# MAIN.net
KiCad netlist of a schematic drawn in Altium Designer
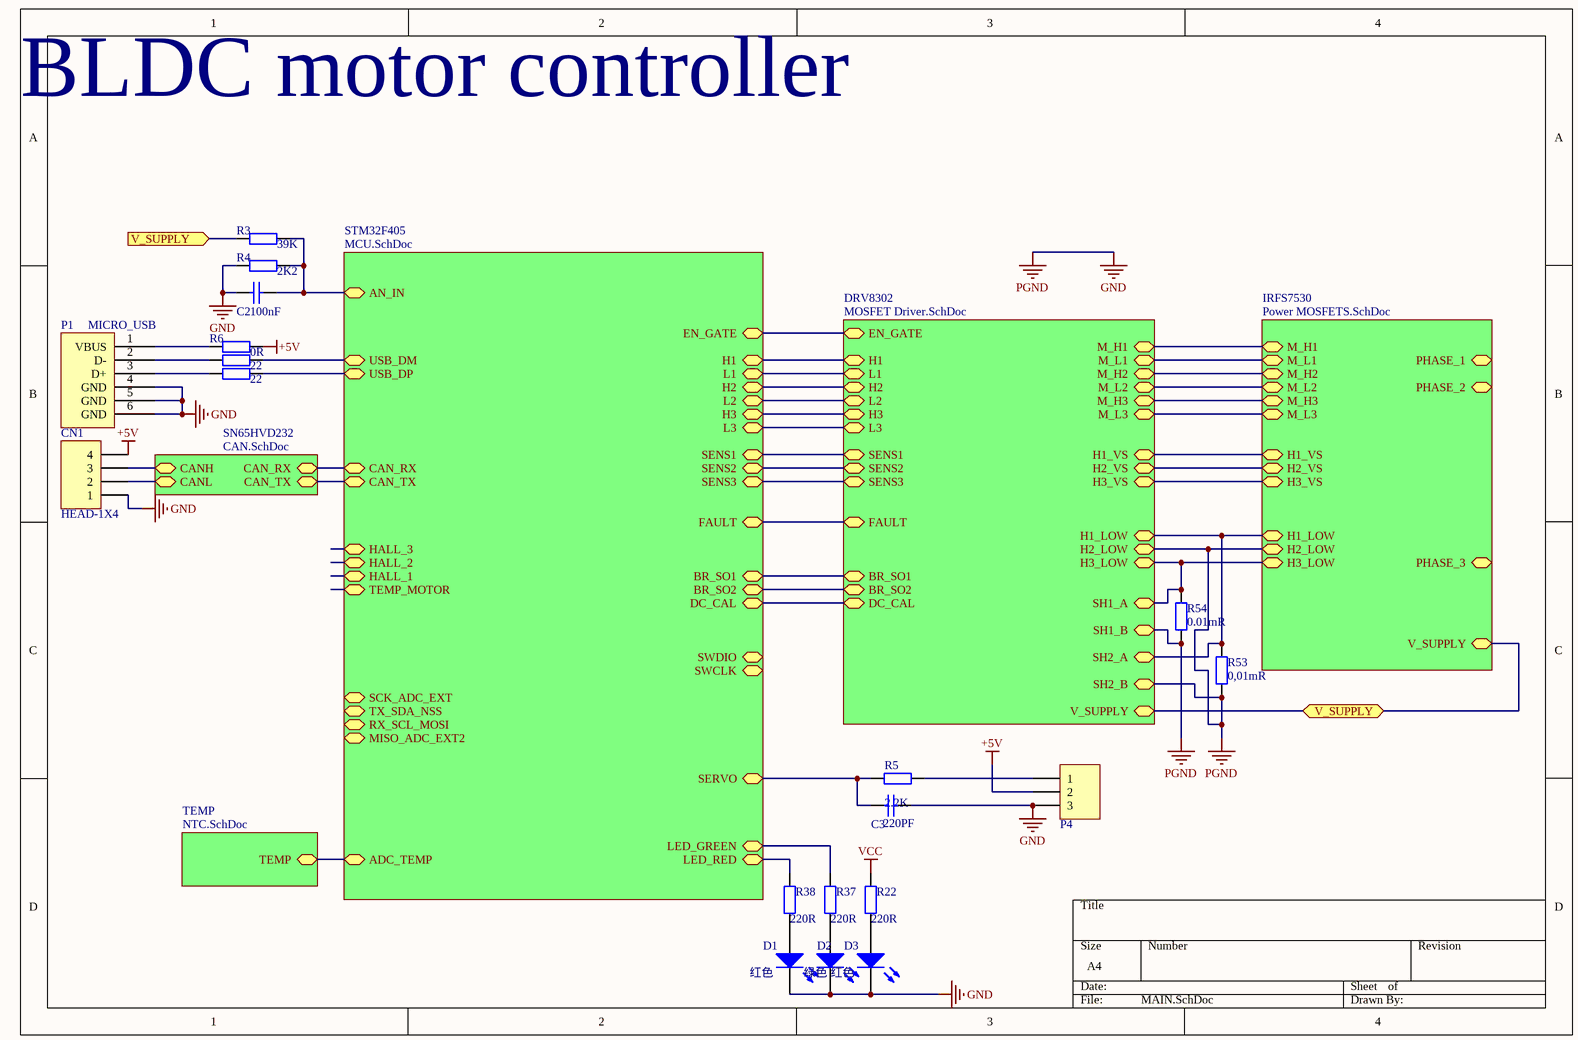
[diagram p0: MAIN.SchDoc]

(export (version "E")
  (design (tool "Eeschema 10.0.6"))
  (components
    (comp (ref "C2")
      (value "100nF")
      (footprint "C-0603")
      (description "Capacitor")
      (fields (field (name "Comment") "CAP") (field (name "PUBLISHER") "Altium Limited"))
      (libsource (lib "TAOXUN") (part "CAP"))
    )
    (comp (ref "C3")
      (value "220PF")
      (footprint "C-0603")
      (description "Capacitor")
      (fields (field (name "PUBLISHER") "Altium Limited"))
      (libsource (lib "TAOXUN") (part "CAP"))
    )
    (comp (ref "CN1")
      (value "HEAD-1X4")
      (footprint "H-1X4")
      (description "Header, 4-Pin")
      (fields (field (name "PUBLISHER") "Altium Limited"))
      (libsource (lib "TAOXUN") (part "HEAD-1X4"))
    )
    (comp (ref "D1")
      (value "红色")
      (footprint "LED0603")
      (description "Typical RED, GREEN, YELLOW, AMBER GaAs LED")
      (fields (field (name "PUBLISHER") "Altium Limited"))
      (libsource (lib "TAOXUN") (part "LED2"))
    )
    (comp (ref "D2")
      (value "绿色")
      (footprint "LED0603")
      (description "Typical RED, GREEN, YELLOW, AMBER GaAs LED")
      (fields (field (name "PUBLISHER") "Altium Limited"))
      (libsource (lib "TAOXUN") (part "LED2"))
    )
    (comp (ref "D3")
      (value "红色")
      (footprint "LED0603")
      (description "Typical RED, GREEN, YELLOW, AMBER GaAs LED")
      (fields (field (name "PUBLISHER") "Altium Limited"))
      (libsource (lib "TAOXUN") (part "LED2"))
    )
    (comp (ref "P1")
      (value "MICRO_USB")
      (footprint "MicroUSB")
      (libsource (lib "Control_PT") (part "MINI_USB"))
    )
    (comp (ref "P4")
      (value "Header 3")
      (footprint "HDR3X1_A")
      (description "接插件")
      (fields (field (name "PUBLISHER") "Altium Limited"))
      (libsource (lib "TAOXUN") (part "Header 3_1"))
    )
    (comp (ref "R3")
      (value "39K")
      (footprint "0402")
      (description "贴片电阻")
      (fields (field (name "PUBLISHER") "Altium Limited"))
      (libsource (lib "TAOXUN") (part "Res1"))
    )
    (comp (ref "R4")
      (value "2K2")
      (footprint "0402")
      (description "贴片电阻")
      (fields (field (name "Comment") "2.2K") (field (name "PUBLISHER") "Altium Limited"))
      (libsource (lib "TAOXUN") (part "Res1"))
    )
    (comp (ref "R5")
      (value "2.2K")
      (footprint "0402")
      (description "贴片电阻")
      (fields (field (name "PUBLISHER") "Altium Limited"))
      (libsource (lib "TAOXUN") (part "Res1"))
    )
    (comp (ref "R6")
      (value "0R")
      (footprint "0603-2")
      (description "贴片电阻")
      (fields (field (name "PUBLISHER") "Altium Limited"))
      (libsource (lib "TAOXUN") (part "Res1"))
    )
    (comp (ref "R14")
      (value "22")
      (footprint "LC-0402")
      (description "贴片电阻")
      (fields (field (name "Comment") "22R") (field (name "PUBLISHER") "Altium Limited"))
      (libsource (lib "TAOXUN") (part "Res1"))
    )
    (comp (ref "R15")
      (value "22")
      (footprint "LC-0402")
      (description "贴片电阻")
      (fields (field (name "Comment") "22R") (field (name "PUBLISHER") "Altium Limited"))
      (libsource (lib "TAOXUN") (part "Res1"))
    )
    (comp (ref "R22")
      (value "220R")
      (footprint "0402")
      (description "贴片电阻")
      (fields (field (name "PUBLISHER") "Altium Limited"))
      (libsource (lib "") (part "Res1_1"))
    )
    (comp (ref "R37")
      (value "220R")
      (footprint "0402")
      (description "贴片电阻")
      (fields (field (name "PUBLISHER") "Altium Limited"))
      (libsource (lib "") (part "Res1_1"))
    )
    (comp (ref "R38")
      (value "220R")
      (footprint "0402")
      (description "贴片电阻")
      (fields (field (name "PUBLISHER") "Altium Limited"))
      (libsource (lib "") (part "Res1_1"))
    )
    (comp (ref "R53")
      (value "0,01mR")
      (footprint "2512")
      (description "贴片电阻")
      (fields (field (name "Comment") "0.001R") (field (name "PUBLISHER") "Altium Limited"))
      (libsource (lib "") (part "Res1_2"))
    )
    (comp (ref "R54")
      (value "0.01mR")
      (footprint "2512")
      (description "贴片电阻")
      (fields (field (name "Comment") "0.001R") (field (name "PUBLISHER") "Altium Limited"))
      (libsource (lib "") (part "Res1_2"))
    )
  )
  (nets
    (net (code "1") (name "+5V") (class "Default")
      (node (ref "CN1") (pin "4") (pinfunction "4_4") (pintype "passive"))
      (node (ref "P4") (pin "2") (pinfunction "2_2") (pintype "passive"))
      (node (ref "R6") (pin "2") (pinfunction "2_2") (pintype "passive"))
    )
    (net (code "3") (name "/AN_IN") (class "Default")
      (node (ref "C2") (pin "2") (pinfunction "2_2") (pintype "passive"))
      (node (ref "R3") (pin "2") (pinfunction "2_2") (pintype "passive"))
      (node (ref "R4") (pin "2") (pinfunction "2_2") (pintype "passive"))
    )
    (net (code "6") (name "/CANH") (class "Default")
      (node (ref "CN1") (pin "3") (pinfunction "3_3") (pintype "passive"))
    )
    (net (code "7") (name "/CANL") (class "Default")
      (node (ref "CN1") (pin "2") (pinfunction "2_2") (pintype "passive"))
    )
    (net (code "14") (name "/H1_LOW") (class "Default")
      (node (ref "R53") (pin "1") (pinfunction "1_1") (pintype "passive"))
    )
    (net (code "19") (name "/H3_LOW") (class "Default")
      (node (ref "R54") (pin "1") (pinfunction "1_1") (pintype "passive"))
    )
    (net (code "27") (name "/LED_GREEN") (class "Default")
      (node (ref "R37") (pin "2") (pinfunction "2_2") (pintype "passive"))
    )
    (net (code "28") (name "/LED_RED") (class "Default")
      (node (ref "R38") (pin "2") (pinfunction "2_2") (pintype "passive"))
    )
    (net (code "44") (name "/SERVO") (class "Default")
      (node (ref "C3") (pin "1") (pinfunction "1_1") (pintype "passive"))
      (node (ref "R5") (pin "1") (pinfunction "1_1") (pintype "passive"))
    )
    (net (code "49") (name "/USB_DM") (class "Default")
      (node (ref "R14") (pin "2") (pinfunction "2_2") (pintype "passive"))
    )
    (net (code "50") (name "/USB_DP") (class "Default")
      (node (ref "R15") (pin "2") (pinfunction "2_2") (pintype "passive"))
    )
    (net (code "51") (name "/V_SUPPLY") (class "Default")
      (node (ref "R3") (pin "1") (pinfunction "1_1") (pintype "passive"))
    )
    (net (code "52") (name "GND") (class "Default")
      (node (ref "C2") (pin "1") (pinfunction "1_1") (pintype "passive"))
      (node (ref "C3") (pin "2") (pinfunction "2_2") (pintype "passive"))
      (node (ref "CN1") (pin "1") (pinfunction "1_1") (pintype "passive"))
      (node (ref "D1") (pin "2") (pinfunction "K_2") (pintype "passive"))
      (node (ref "D2") (pin "2") (pinfunction "K_2") (pintype "passive"))
      (node (ref "D3") (pin "2") (pinfunction "K_2") (pintype "passive"))
      (node (ref "P1") (pin "4") (pinfunction "GND_4") (pintype "passive"))
      (node (ref "P1") (pin "5") (pinfunction "GND_5") (pintype "passive"))
      (node (ref "P1") (pin "6") (pinfunction "GND_6") (pintype "passive"))
      (node (ref "P4") (pin "3") (pinfunction "3_3") (pintype "passive"))
      (node (ref "R4") (pin "1") (pinfunction "1_1") (pintype "passive"))
      (node (ref "R53") (pin "2") (pinfunction "2_2") (pintype "passive"))
      (node (ref "R54") (pin "2") (pinfunction "2_2") (pintype "passive"))
    )
    (net (code "53") (name "Net-(D1-A)") (class "Default")
      (node (ref "D1") (pin "1") (pinfunction "A_1") (pintype "passive"))
      (node (ref "R38") (pin "1") (pinfunction "1_1") (pintype "passive"))
    )
    (net (code "54") (name "Net-(D2-A)") (class "Default")
      (node (ref "D2") (pin "1") (pinfunction "A_1") (pintype "passive"))
      (node (ref "R37") (pin "1") (pinfunction "1_1") (pintype "passive"))
    )
    (net (code "55") (name "Net-(D3-A)") (class "Default")
      (node (ref "D3") (pin "1") (pinfunction "A_1") (pintype "passive"))
      (node (ref "R22") (pin "1") (pinfunction "1_1") (pintype "passive"))
    )
    (net (code "56") (name "Net-(P1-D+)") (class "Default")
      (node (ref "P1") (pin "3") (pinfunction "D+_3") (pintype "passive"))
      (node (ref "R15") (pin "1") (pinfunction "1_1") (pintype "passive"))
    )
    (net (code "57") (name "Net-(P1-D-)") (class "Default")
      (node (ref "P1") (pin "2") (pinfunction "D-_2") (pintype "passive"))
      (node (ref "R14") (pin "1") (pinfunction "1_1") (pintype "passive"))
    )
    (net (code "58") (name "Net-(P1-VBUS)") (class "Default")
      (node (ref "P1") (pin "1") (pinfunction "VBUS_1") (pintype "passive"))
      (node (ref "R6") (pin "1") (pinfunction "1_1") (pintype "passive"))
    )
    (net (code "59") (name "Net-(P4-Pad1)") (class "Default")
      (node (ref "P4") (pin "1") (pinfunction "1_1") (pintype "passive"))
      (node (ref "R5") (pin "2") (pinfunction "2_2") (pintype "passive"))
    )
    (net (code "60") (name "VCC") (class "Default")
      (node (ref "R22") (pin "2") (pinfunction "2_2") (pintype "passive"))
    )
  )
)
